# design.net
KiCad netlist of a schematic drawn in Altium Designer
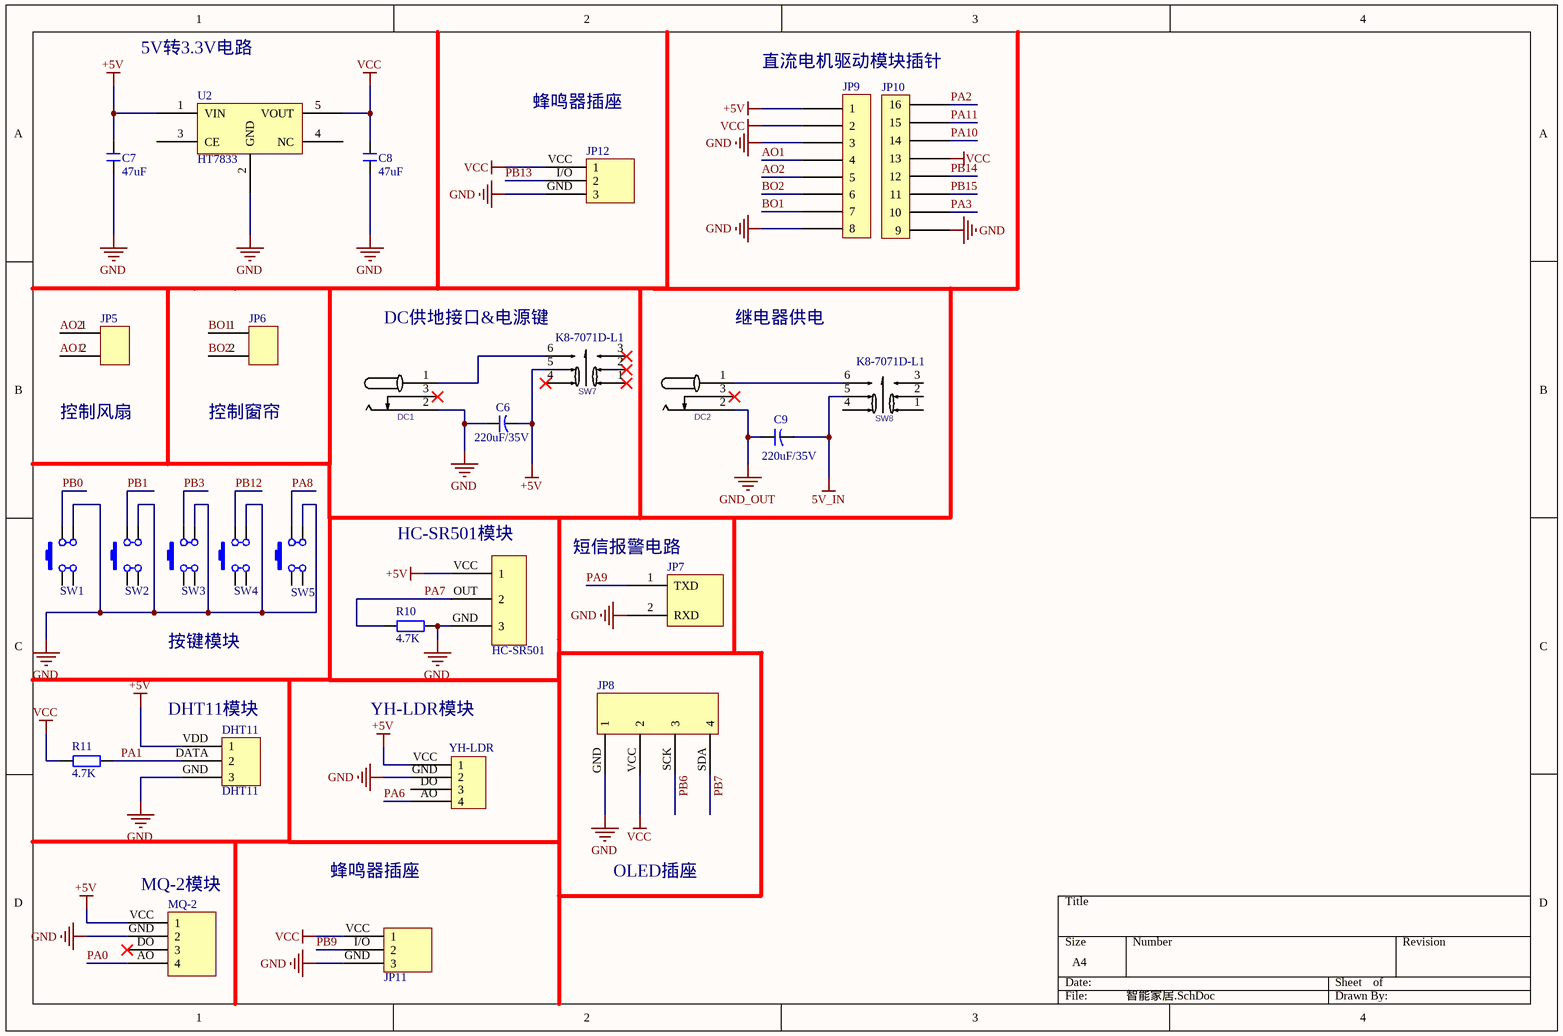
[diagram p0: 智能家居.SchDoc]

(export (version "E")
  (design (tool "Eeschema 10.0.6"))
  (components
    (comp (ref "C6") (value "CAP2") (footprint "CAP") (libsource (lib "智能家居") (part "CAP2")))
    (comp (ref "C7")
      (value "47uF")
      (footprint "47uF")
      (description "贴片电容")
      (libsource (lib "0.1 - 电阻-电容-电感") (part "C"))
    )
    (comp (ref "C8")
      (value "47uF")
      (footprint "47uF")
      (description "贴片电容")
      (libsource (lib "0.1 - 电阻-电容-电感") (part "C"))
    )
    (comp (ref "C9") (value "220uF/35V") (footprint "CAP") (libsource (lib "智能家居") (part "CAP2")))
    (comp (ref "DC1")
      (value "DC005")
      (footprint "DC005")
      (fields (field (name "MANUFACTURER") "SHOU HAN(首韩)"))
      (libsource (lib "altium-import") (part "root_0_DC005_"))
    )
    (comp (ref "DC2")
      (value "DC005")
      (footprint "DC005")
      (fields (field (name "MANUFACTURER") "SHOU HAN(首韩)"))
      (libsource (lib "altium-import") (part "root_0_DC005_"))
    )
    (comp (ref "DHT11")
      (value "DHT11")
      (footprint "HAR1X3-3")
      (description "温湿度传感器")
      (libsource (lib "智能家居") (part "DHT11"))
    )
    (comp (ref "HC-SR1")
      (value "HC-SR501")
      (footprint "HDR1X3-2")
      (description "人体红外热释电传感器")
      (libsource (lib "智能家居") (part "HC-SR501"))
    )
    (comp (ref "JP5")
      (value "JP1")
      (footprint "HDR1X2")
      (description "插针")
      (libsource (lib "智能家居") (part "JP1"))
    )
    (comp (ref "JP6")
      (value "JP1")
      (footprint "HDR1X2")
      (description "插针")
      (libsource (lib "智能家居") (part "JP1"))
    )
    (comp (ref "JP7")
      (value "JP2")
      (footprint "HDR1X2")
      (description "USB转串口")
      (libsource (lib "智能家居") (part "JP2"))
    )
    (comp (ref "JP8")
      (value "JP7")
      (footprint "HAR1X4-2")
      (description "OLED引脚插针")
      (libsource (lib "智能家居") (part "JP7"))
    )
    (comp (ref "JP9")
      (value "JP5")
      (footprint "HDR1X8")
      (description "直流电机驱动模块插针第一列")
      (libsource (lib "智能家居") (part "JP5"))
    )
    (comp (ref "JP10")
      (value "JP6")
      (footprint "HDR1X8-2")
      (description "直流电机驱动模块第二列")
      (libsource (lib "智能家居") (part "JP6"))
    )
    (comp (ref "JP11")
      (value "JP11")
      (footprint "HDR1X3-3")
      (description "蜂鸣器插针")
      (libsource (lib "智能家居") (part "JP11"))
    )
    (comp (ref "JP12") (value "JP12") (footprint "HDR1X3-3") (libsource (lib "智能家居") (part "JP12")))
    (comp (ref "MQ-2")
      (value "MQ-2")
      (footprint "HAR1X4-4")
      (description "烟雾传感器")
      (libsource (lib "智能家居") (part "MQ-2"))
    )
    (comp (ref "R10")
      (value "4.7K")
      (footprint "R 0805_L")
      (description "贴片电阻")
      (fields (field (name "版权归属") "来自淘宝 ID：黄晶宝石"))
      (libsource (lib "0.1 - 电阻-电容-电感") (part "R"))
    )
    (comp (ref "R11")
      (value "4.7K")
      (footprint "R 0805_L")
      (description "贴片电阻")
      (fields (field (name "版权归属") "来自淘宝 ID：黄晶宝石"))
      (libsource (lib "0.1 - 电阻-电容-电感") (part "R"))
    )
    (comp (ref "SW1")
      (value "KEY")
      (footprint "KEY")
      (description "普通按键")
      (libsource (lib "智能家居") (part "KEY"))
    )
    (comp (ref "SW2")
      (value "KEY")
      (footprint "KEY")
      (description "普通按键")
      (libsource (lib "智能家居") (part "KEY"))
    )
    (comp (ref "SW3")
      (value "KEY")
      (footprint "KEY")
      (description "普通按键")
      (libsource (lib "智能家居") (part "KEY"))
    )
    (comp (ref "SW4")
      (value "KEY")
      (footprint "KEY")
      (description "普通按键")
      (libsource (lib "智能家居") (part "KEY"))
    )
    (comp (ref "SW5")
      (value "KEY")
      (footprint "KEY")
      (description "普通按键")
      (libsource (lib "智能家居") (part "KEY"))
    )
    (comp (ref "SW7")
      (value "K8-7071D-L1")
      (footprint "K8")
      (fields (field (name "MANUFACTURER") "韩国韩荣"))
      (libsource (lib "altium-import") (part "root_1_K8-7071D-L1_"))
    )
    (comp (ref "SW8")
      (value "K8-7071D-L1")
      (footprint "K8")
      (fields (field (name "MANUFACTURER") "韩国韩荣"))
      (libsource (lib "altium-import") (part "root_1_K8-7071D-L1_"))
    )
    (comp (ref "U2")
      (value "HT7833")
      (footprint "HT7833")
      (description "5V转3.3V电路")
      (libsource (lib "智能家居") (part "HT7833"))
    )
    (comp (ref "YH-LDR1")
      (value "YH-LDR")
      (footprint "HAR1X4-4")
      (description "光敏传感器")
      (libsource (lib "智能家居") (part "YH-LDR"))
    )
  )
  (nets
    (net (code "1") (name "+5V") (class "Default")
      (node (ref "C6") (pin "1") (pinfunction "1_1") (pintype "passive"))
      (node (ref "C7") (pin "2") (pinfunction "2_2") (pintype "passive"))
      (node (ref "DHT11") (pin "VDD") (pinfunction "1_VDD") (pintype "passive"))
      (node (ref "HC-SR1") (pin "VCC") (pinfunction "1_VCC") (pintype "passive"))
      (node (ref "JP9") (pin "1") (pinfunction "1_1") (pintype "passive"))
      (node (ref "MQ-2") (pin "VCC") (pinfunction "1_VCC") (pintype "passive"))
      (node (ref "SW7") (pin "5") (pinfunction "5_5") (pintype "passive"))
      (node (ref "U2") (pin "1") (pinfunction "VIN_1") (pintype "passive"))
      (node (ref "YH-LDR1") (pin "VCC") (pinfunction "1_VCC") (pintype "passive"))
    )
    (net (code "3") (name "/AO1") (class "Default")
      (node (ref "JP5") (pin "2") (pintype "passive"))
      (node (ref "JP9") (pin "4") (pinfunction "4_4") (pintype "passive"))
    )
    (net (code "4") (name "/AO2") (class "Default")
      (node (ref "JP5") (pin "1") (pintype "passive"))
      (node (ref "JP9") (pin "5") (pinfunction "5_5") (pintype "passive"))
    )
    (net (code "5") (name "/BO1") (class "Default")
      (node (ref "JP6") (pin "1") (pintype "passive"))
      (node (ref "JP9") (pin "7") (pinfunction "7_7") (pintype "passive"))
    )
    (net (code "6") (name "/BO2") (class "Default")
      (node (ref "JP6") (pin "2") (pintype "passive"))
      (node (ref "JP9") (pin "6") (pinfunction "6_6") (pintype "passive"))
    )
    (net (code "7") (name "/PA0") (class "Default")
      (node (ref "MQ-2") (pin "AO") (pinfunction "4_AO") (pintype "passive"))
    )
    (net (code "8") (name "/PA1") (class "Default")
      (node (ref "DHT11") (pin "DATA") (pinfunction "2_DATA") (pintype "passive"))
      (node (ref "R11") (pin "1") (pinfunction "1_1") (pintype "passive"))
    )
    (net (code "9") (name "/PA2") (class "Default")
      (node (ref "JP10") (pin "16") (pinfunction "16_16") (pintype "passive"))
    )
    (net (code "10") (name "/PA3") (class "Default")
      (node (ref "JP10") (pin "10") (pinfunction "10_10") (pintype "passive"))
    )
    (net (code "11") (name "/PA6") (class "Default")
      (node (ref "YH-LDR1") (pin "AO") (pinfunction "4_AO") (pintype "passive"))
    )
    (net (code "12") (name "/PA7") (class "Default")
      (node (ref "HC-SR1") (pin "OUT") (pinfunction "2_OUT") (pintype "passive"))
      (node (ref "R10") (pin "1") (pinfunction "1_1") (pintype "passive"))
    )
    (net (code "13") (name "/PA8") (class "Default") (node (ref "SW5") (pin "2") (pintype "passive")))
    (net (code "14") (name "/PA9") (class "Default")
      (node (ref "JP7") (pin "1") (pinfunction "TXD_1") (pintype "passive"))
    )
    (net (code "15") (name "/PA10") (class "Default")
      (node (ref "JP10") (pin "14") (pinfunction "14_14") (pintype "passive"))
    )
    (net (code "16") (name "/PA11") (class "Default")
      (node (ref "JP10") (pin "15") (pinfunction "15_15") (pintype "passive"))
    )
    (net (code "17") (name "/PB0") (class "Default") (node (ref "SW1") (pin "2") (pintype "passive")))
    (net (code "18") (name "/PB1") (class "Default") (node (ref "SW2") (pin "2") (pintype "passive")))
    (net (code "19") (name "/PB3") (class "Default") (node (ref "SW3") (pin "2") (pintype "passive")))
    (net (code "20") (name "/PB6") (class "Default")
      (node (ref "JP8") (pin "SCK") (pinfunction "3_SCK") (pintype "passive"))
    )
    (net (code "21") (name "/PB7") (class "Default")
      (node (ref "JP8") (pin "SDA") (pinfunction "4_SDA") (pintype "passive"))
    )
    (net (code "22") (name "/PB9") (class "Default")
      (node (ref "JP11") (pin "I/O") (pinfunction "2_I/O") (pintype "passive"))
    )
    (net (code "23") (name "/PB12") (class "Default") (node (ref "SW4") (pin "2") (pintype "passive")))
    (net (code "24") (name "/PB13") (class "Default")
      (node (ref "JP12") (pin "I/O") (pinfunction "2_I/O") (pintype "passive"))
    )
    (net (code "25") (name "/PB14") (class "Default")
      (node (ref "JP10") (pin "12") (pinfunction "12_12") (pintype "passive"))
    )
    (net (code "26") (name "/PB15") (class "Default")
      (node (ref "JP10") (pin "11") (pinfunction "11_11") (pintype "passive"))
    )
    (net (code "27") (name "5V_IN") (class "Default")
      (node (ref "C9") (pin "1") (pinfunction "1_1") (pintype "passive"))
      (node (ref "SW8") (pin "5") (pinfunction "5_5") (pintype "passive"))
    )
    (net (code "28") (name "GND") (class "Default")
      (node (ref "C6") (pin "2") (pinfunction "2_2") (pintype "passive"))
      (node (ref "C7") (pin "1") (pinfunction "1_1") (pintype "passive"))
      (node (ref "C8") (pin "1") (pinfunction "1_1") (pintype "passive"))
      (node (ref "DC1") (pin "2") (pinfunction "2_2") (pintype "passive"))
      (node (ref "DHT11") (pin "GND") (pinfunction "3_GND") (pintype "passive"))
      (node (ref "HC-SR1") (pin "GND") (pinfunction "3_GND") (pintype "passive"))
      (node (ref "JP10") (pin "9") (pinfunction "9_9") (pintype "passive"))
      (node (ref "JP11") (pin "GND") (pinfunction "3_GND") (pintype "passive"))
      (node (ref "JP12") (pin "GND") (pinfunction "3_GND") (pintype "passive"))
      (node (ref "JP7") (pin "2") (pinfunction "RXD_2") (pintype "passive"))
      (node (ref "JP8") (pin "GND") (pinfunction "1_GND") (pintype "passive"))
      (node (ref "JP9") (pin "3") (pinfunction "3_3") (pintype "passive"))
      (node (ref "JP9") (pin "8") (pinfunction "8_8") (pintype "passive"))
      (node (ref "MQ-2") (pin "GND") (pinfunction "2_GND") (pintype "passive"))
      (node (ref "R10") (pin "2") (pinfunction "2_2") (pintype "passive"))
      (node (ref "SW1") (pin "4") (pintype "passive"))
      (node (ref "SW2") (pin "4") (pintype "passive"))
      (node (ref "SW3") (pin "4") (pintype "passive"))
      (node (ref "SW4") (pin "4") (pintype "passive"))
      (node (ref "SW5") (pin "4") (pintype "passive"))
      (node (ref "U2") (pin "2") (pinfunction "GND_2") (pintype "passive"))
      (node (ref "YH-LDR1") (pin "GND") (pinfunction "2_GND") (pintype "passive"))
    )
    (net (code "29") (name "GND_OUT") (class "Default")
      (node (ref "C9") (pin "2") (pinfunction "2_2") (pintype "passive"))
      (node (ref "DC2") (pin "2") (pinfunction "2_2") (pintype "passive"))
    )
    (net (code "30") (name "Net-(DC1-Pad1)") (class "Default")
      (node (ref "DC1") (pin "1") (pinfunction "1_1") (pintype "passive"))
      (node (ref "SW7") (pin "6") (pinfunction "6_6") (pintype "passive"))
    )
    (net (code "31") (name "Net-(DC2-Pad1)") (class "Default")
      (node (ref "DC2") (pin "1") (pinfunction "1_1") (pintype "passive"))
      (node (ref "SW8") (pin "6") (pinfunction "6_6") (pintype "passive"))
    )
    (net (code "32") (name "VCC") (class "Default")
      (node (ref "C8") (pin "2") (pinfunction "2_2") (pintype "passive"))
      (node (ref "JP10") (pin "13") (pinfunction "13_13") (pintype "passive"))
      (node (ref "JP11") (pin "VCC") (pinfunction "1_VCC") (pintype "passive"))
      (node (ref "JP12") (pin "VCC") (pinfunction "1_VCC") (pintype "passive"))
      (node (ref "JP8") (pin "VCC") (pinfunction "2_VCC") (pintype "passive"))
      (node (ref "JP9") (pin "2") (pinfunction "2_2") (pintype "passive"))
      (node (ref "R11") (pin "2") (pinfunction "2_2") (pintype "passive"))
      (node (ref "U2") (pin "5") (pinfunction "VOUT_5") (pintype "passive"))
    )
    (net (code "33") (name "unconnected-(DC1-Pad3)") (class "Default")
      (node (ref "DC1") (pin "3") (pinfunction "3_3") (pintype "passive+no_connect"))
    )
    (net (code "34") (name "unconnected-(DC2-Pad3)") (class "Default")
      (node (ref "DC2") (pin "3") (pinfunction "3_3") (pintype "passive+no_connect"))
    )
    (net (code "35") (name "unconnected-(MQ-2-3-PadDO)") (class "Default")
      (node (ref "MQ-2") (pin "DO") (pinfunction "3_DO") (pintype "passive+no_connect"))
    )
    (net (code "36") (name "unconnected-(SW1-Pad1)") (class "Default")
      (node (ref "SW1") (pin "1") (pintype "passive"))
    )
    (net (code "37") (name "unconnected-(SW1-Pad3)") (class "Default")
      (node (ref "SW1") (pin "3") (pintype "passive"))
    )
    (net (code "38") (name "unconnected-(SW2-Pad1)") (class "Default")
      (node (ref "SW2") (pin "1") (pintype "passive"))
    )
    (net (code "39") (name "unconnected-(SW2-Pad3)") (class "Default")
      (node (ref "SW2") (pin "3") (pintype "passive"))
    )
    (net (code "40") (name "unconnected-(SW3-Pad1)") (class "Default")
      (node (ref "SW3") (pin "1") (pintype "passive"))
    )
    (net (code "41") (name "unconnected-(SW3-Pad3)") (class "Default")
      (node (ref "SW3") (pin "3") (pintype "passive"))
    )
    (net (code "42") (name "unconnected-(SW4-Pad1)") (class "Default")
      (node (ref "SW4") (pin "1") (pintype "passive"))
    )
    (net (code "43") (name "unconnected-(SW4-Pad3)") (class "Default")
      (node (ref "SW4") (pin "3") (pintype "passive"))
    )
    (net (code "44") (name "unconnected-(SW5-Pad1)") (class "Default")
      (node (ref "SW5") (pin "1") (pintype "passive"))
    )
    (net (code "45") (name "unconnected-(SW5-Pad3)") (class "Default")
      (node (ref "SW5") (pin "3") (pintype "passive"))
    )
    (net (code "46") (name "unconnected-(SW7-Pad1)") (class "Default")
      (node (ref "SW7") (pin "1") (pinfunction "1_1") (pintype "passive+no_connect"))
    )
    (net (code "47") (name "unconnected-(SW7-Pad2)") (class "Default")
      (node (ref "SW7") (pin "2") (pinfunction "2_2") (pintype "passive+no_connect"))
    )
    (net (code "48") (name "unconnected-(SW7-Pad3)") (class "Default")
      (node (ref "SW7") (pin "3") (pinfunction "3_3") (pintype "passive+no_connect"))
    )
    (net (code "49") (name "unconnected-(SW7-Pad4)") (class "Default")
      (node (ref "SW7") (pin "4") (pinfunction "4_4") (pintype "passive+no_connect"))
    )
    (net (code "50") (name "unconnected-(SW8-Pad1)") (class "Default")
      (node (ref "SW8") (pin "1") (pinfunction "1_1") (pintype "passive"))
    )
    (net (code "51") (name "unconnected-(SW8-Pad2)") (class "Default")
      (node (ref "SW8") (pin "2") (pinfunction "2_2") (pintype "passive"))
    )
    (net (code "52") (name "unconnected-(SW8-Pad3)") (class "Default")
      (node (ref "SW8") (pin "3") (pinfunction "3_3") (pintype "passive"))
    )
    (net (code "53") (name "unconnected-(SW8-Pad4)") (class "Default")
      (node (ref "SW8") (pin "4") (pinfunction "4_4") (pintype "passive"))
    )
    (net (code "54") (name "unconnected-(U2-CE-Pad3)") (class "Default")
      (node (ref "U2") (pin "3") (pinfunction "CE_3") (pintype "passive"))
    )
    (net (code "55") (name "unconnected-(U2-NC-Pad4)") (class "Default")
      (node (ref "U2") (pin "4") (pinfunction "NC_4") (pintype "passive"))
    )
    (net (code "56") (name "unconnected-(YH-LDR1-3-PadDO)") (class "Default")
      (node (ref "YH-LDR1") (pin "DO") (pinfunction "3_DO") (pintype "passive"))
    )
  )
)
